# 04_MCU.net
KiCad netlist of a schematic drawn in Altium Designer
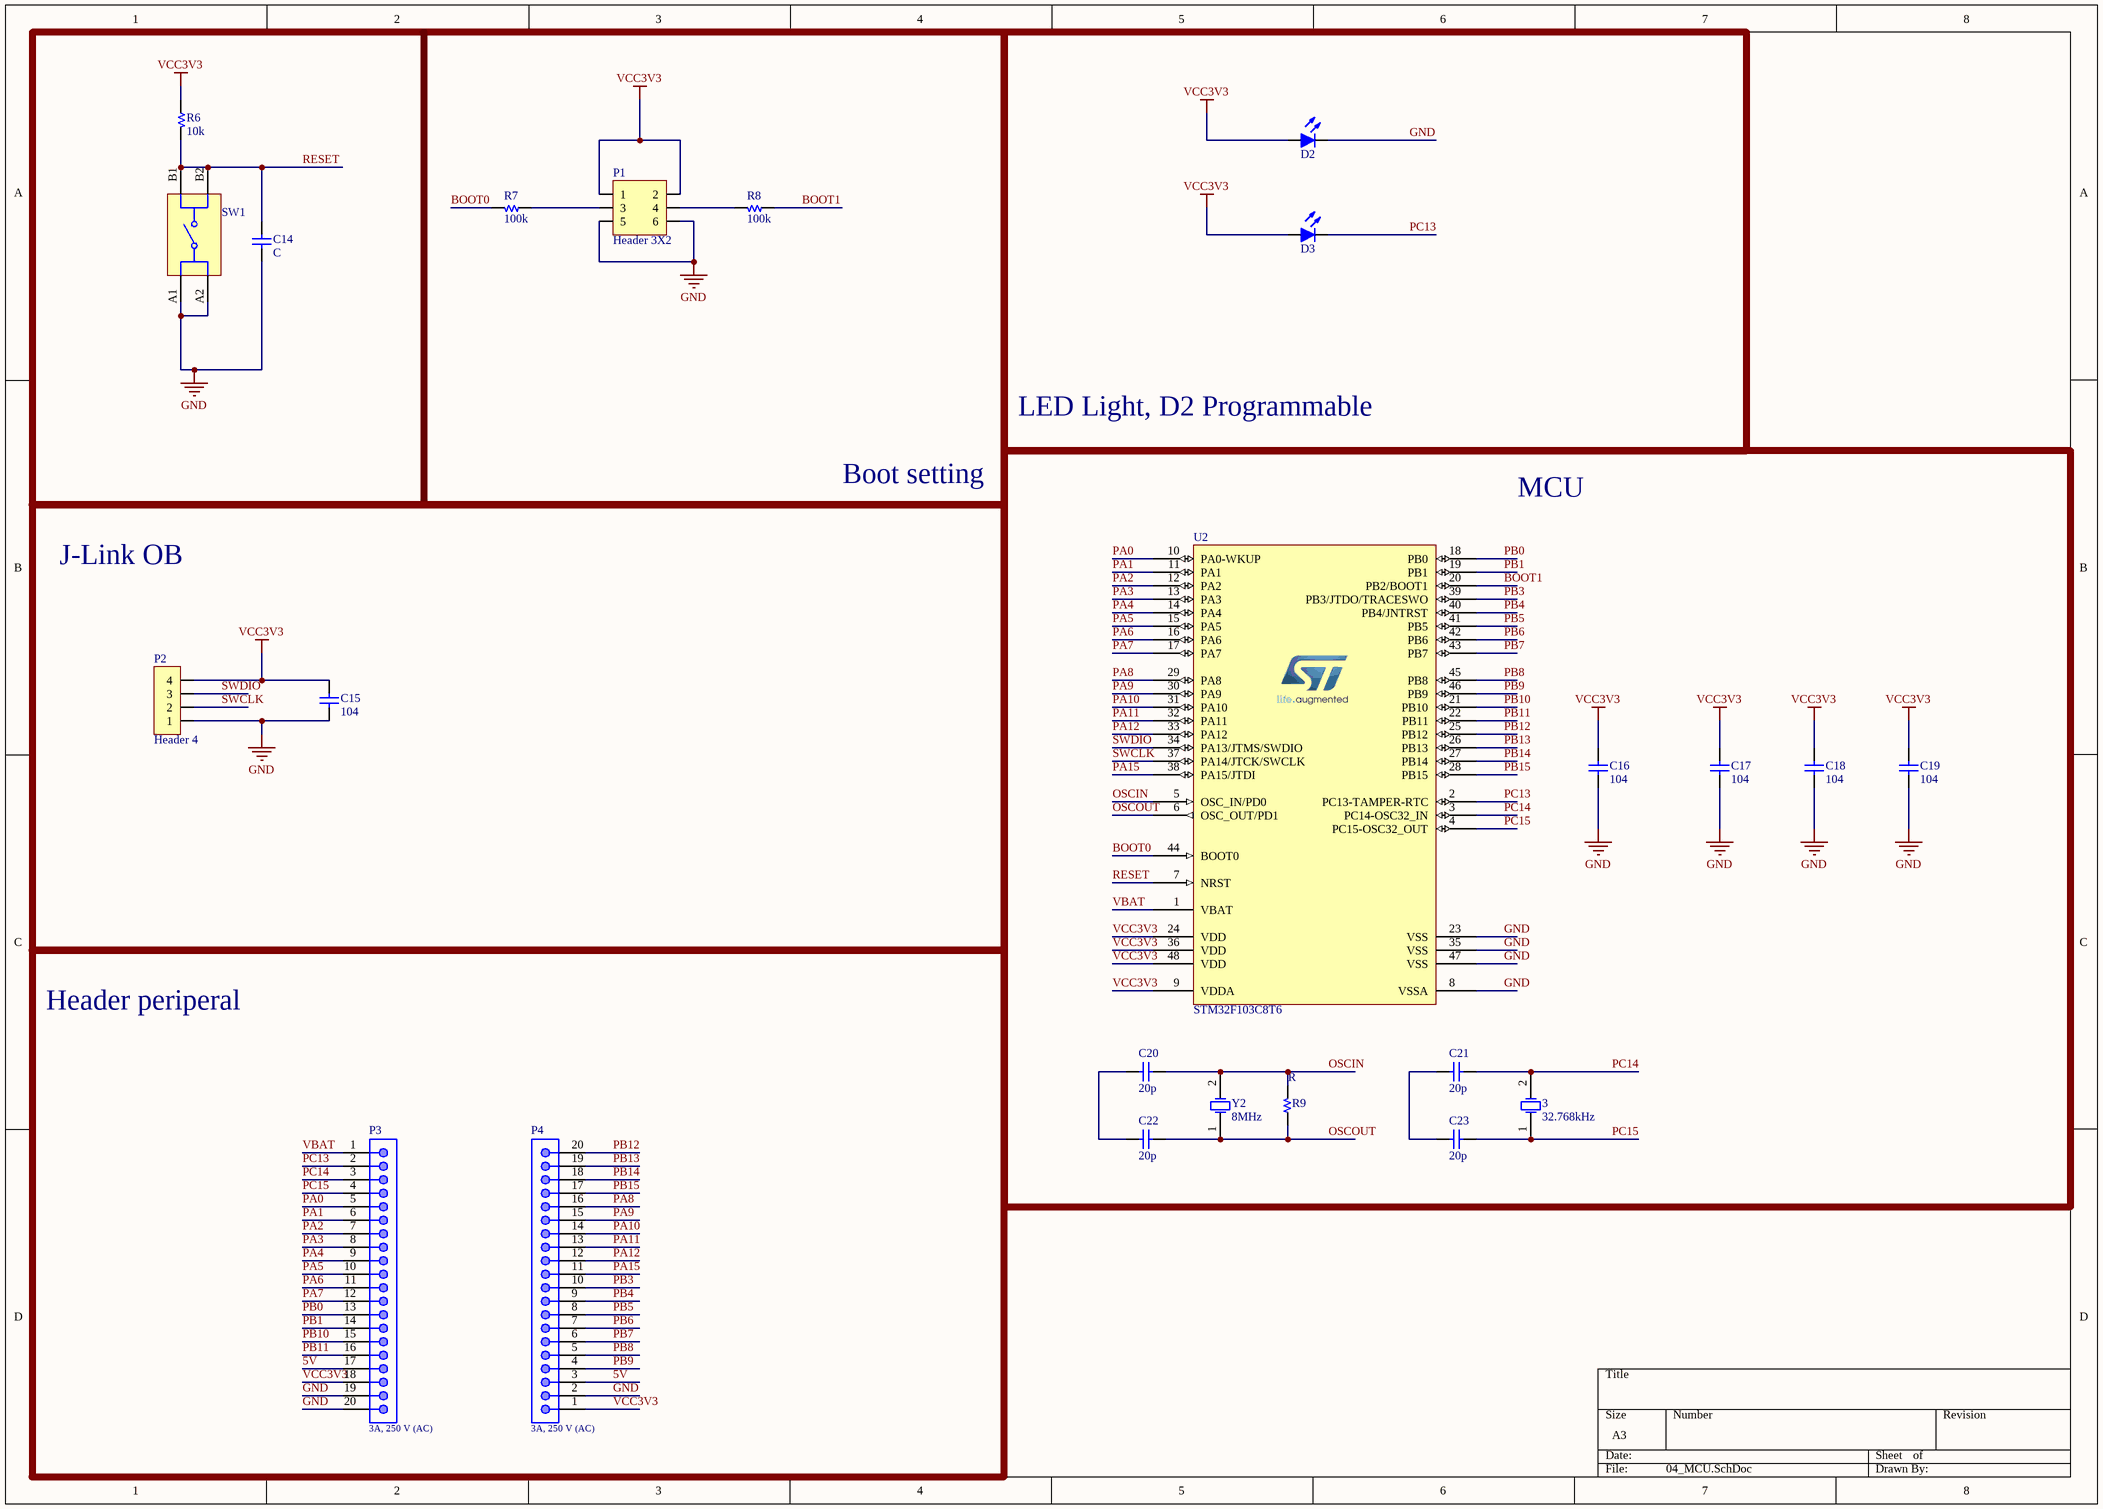
[diagram p0: 04_MCU.SchDoc]

(export (version "E")
  (design (tool "Eeschema 10.0.6"))
  (components
    (comp (ref "3")
      (value "32.768kHz")
      (footprint "XKXGI-SUA-32.768K")
      (description "32.768kHz Surface Mount Crystal 12.5pF ±20ppm ±30ppm SMD3215-2P Crystals ROHS")
      (fields (field (name "LCSC PART #") "C5213671") (field (name "MANUFACTURER") "YXC Crystal Oscillators"))
      (libsource (lib "Altium_XTAL_WATCH") (part "XKXGI-SUA-32.768K"))
    )
    (comp (ref "C14")
      (value "C")
      (footprint "C 0805")
      (description "Capacitor non-pol")
      (libsource (lib "chipfc_libs") (part "Capacitor NP"))
    )
    (comp (ref "C15")
      (value "104")
      (footprint "C 0805")
      (description "Capacitor non-pol")
      (libsource (lib "chipfc_libs") (part "Capacitor NP"))
    )
    (comp (ref "C16")
      (value "104")
      (footprint "C 0805")
      (description "Capacitor non-pol")
      (libsource (lib "chipfc_libs") (part "Capacitor NP"))
    )
    (comp (ref "C17")
      (value "104")
      (footprint "C 0805")
      (description "Capacitor non-pol")
      (libsource (lib "chipfc_libs") (part "Capacitor NP"))
    )
    (comp (ref "C18")
      (value "104")
      (footprint "C 0805")
      (description "Capacitor non-pol")
      (libsource (lib "chipfc_libs") (part "Capacitor NP"))
    )
    (comp (ref "C19")
      (value "104")
      (footprint "C 0805")
      (description "Capacitor non-pol")
      (libsource (lib "chipfc_libs") (part "Capacitor NP"))
    )
    (comp (ref "C20")
      (value "20p")
      (footprint "C 0805")
      (description "Capacitor non-pol")
      (libsource (lib "chipfc_libs") (part "Capacitor NP"))
    )
    (comp (ref "C21")
      (value "20p")
      (footprint "C 0805")
      (description "Capacitor non-pol")
      (libsource (lib "chipfc_libs") (part "Capacitor NP"))
    )
    (comp (ref "C22")
      (value "20p")
      (footprint "C 0805")
      (description "Capacitor non-pol")
      (libsource (lib "chipfc_libs") (part "Capacitor NP"))
    )
    (comp (ref "C23")
      (value "20p")
      (footprint "C 0805")
      (description "Capacitor non-pol")
      (libsource (lib "chipfc_libs") (part "Capacitor NP"))
    )
    (comp (ref "D2")
      (value "Led")
      (footprint "Led 0805")
      (description "Typical LED")
      (libsource (lib "led") (part "Led"))
    )
    (comp (ref "D3")
      (value "Led")
      (footprint "Led 0805")
      (description "Typical LED")
      (libsource (lib "led") (part "Led"))
    )
    (comp (ref "P1")
      (value "Header 3X2")
      (footprint "HDR/Header/6/DL")
      (description "Header, 3-Pin, Dual row")
      (libsource (lib "connectors") (part "Header 3X2"))
    )
    (comp (ref "P2")
      (value "Header 4")
      (footprint "HDR/Header/4")
      (description "Header, 4-Pin")
      (libsource (lib "connectors") (part "Header 4"))
    )
    (comp (ref "P3")
      (value "3A, 250 V (AC)")
      (footprint "61302011121")
      (description "WR-PHD Pin Header, THT, pitch 2.54mm, Single Row, Vertical, 20p")
      (fields
        (field (name "MANUFACTURER PART NUMBER") "61302011121")
        (field (name "MANUFACTURER") "Wurth Elektronik")
      )
      (libsource (lib "WR-PHD_Pin Header_2.54mm") (part "61302011121"))
    )
    (comp (ref "P4")
      (value "3A, 250 V (AC)")
      (footprint "61302011121")
      (description "WR-PHD Pin Header, THT, pitch 2.54mm, Single Row, Vertical, 20p")
      (fields
        (field (name "MANUFACTURER PART NUMBER") "61302011121")
        (field (name "MANUFACTURER") "Wurth Elektronik")
      )
      (libsource (lib "WR-PHD_Pin Header_2.54mm") (part "61302011121"))
    )
    (comp (ref "R6")
      (value "10k")
      (footprint "R 0805")
      (description "Resistor")
      (libsource (lib "chipfc_libs") (part "Resistor"))
    )
    (comp (ref "R7")
      (value "100k")
      (footprint "R 0805")
      (description "Resistor")
      (libsource (lib "chipfc_libs") (part "Resistor"))
    )
    (comp (ref "R8")
      (value "100k")
      (footprint "R 0805")
      (description "Resistor")
      (libsource (lib "chipfc_libs") (part "Resistor"))
    )
    (comp (ref "R9")
      (value "R")
      (footprint "R 0805")
      (description "Resistor")
      (libsource (lib "chipfc_libs") (part "Resistor"))
    )
    (comp (ref "SW1")
      (value "430152043826")
      (footprint "WS-TASV_L6W6H4.3_4301x20438x6")
      (description "WS-TASV SMT Tact Switch, L6 x W6 x H4.3mm, 260g, SPST-NO, 12V, 50mA")
      (fields (field (name "MANUFACTURER") "Wurth Elektronik"))
      (libsource (lib "Button") (part "430152043826"))
    )
    (comp (ref "U2")
      (value "STM32F103C8T6")
      (footprint "STM32F103C8T6")
      (description "ARM Microcontrollers - MCU 32BIT Cortex M3 64KB 20KB RAM 2X12 ADC")
      (fields
        (field (name "MANUFACTURER") "STMicroelectronics")
        (field (name "MANUFACTURER PART NUMBER") "STM32F103C8T6TR")
      )
      (libsource (lib "STM32") (part "STM32F103C8T6"))
    )
    (comp (ref "Y2")
      (value "8MHz")
      (footprint "WE-XTAL_HC49/4HSMX")
      (description "WE-XTAL Quartz Crystal, SMT, HC49/4HSMX, 8MHz, +/-30ppm")
      (fields
        (field (name "MANUFACTURER PART NUMBER") "830003151")
        (field (name "MANUFACTURER") "Wurth Elektronik")
      )
      (libsource (lib "Altium_XTAL_2PIN") (part "071105086016"))
    )
  )
  (nets
    (net (code "1") (name "/5V") (class "Default")
      (node (ref "P3") (pin "17") (pinfunction "17_17") (pintype "passive"))
      (node (ref "P4") (pin "3") (pinfunction "3_3") (pintype "passive"))
    )
    (net (code "2") (name "/BOOT0") (class "Default")
      (node (ref "R7") (pin "2") (pinfunction "2_2") (pintype "passive"))
      (node (ref "U2") (pin "44") (pinfunction "BOOT0_44") (pintype "input"))
    )
    (net (code "3") (name "/BOOT1") (class "Default")
      (node (ref "R8") (pin "1") (pinfunction "1_1") (pintype "passive"))
      (node (ref "U2") (pin "20") (pinfunction "PB2/BOOT1_20") (pintype "bidirectional"))
    )
    (net (code "4") (name "/OSCIN") (class "Default")
      (node (ref "C20") (pin "1") (pinfunction "1_1") (pintype "passive"))
      (node (ref "R9") (pin "2") (pinfunction "2_2") (pintype "passive"))
      (node (ref "U2") (pin "5") (pinfunction "OSC_IN/PD0_5") (pintype "input"))
      (node (ref "Y2") (pin "2") (pinfunction "OSC2_2") (pintype "passive"))
    )
    (net (code "5") (name "/OSCOUT") (class "Default")
      (node (ref "C22") (pin "1") (pinfunction "1_1") (pintype "passive"))
      (node (ref "R9") (pin "1") (pinfunction "1_1") (pintype "passive"))
      (node (ref "U2") (pin "6") (pinfunction "OSC_OUT/PD1_6") (pintype "output"))
      (node (ref "Y2") (pin "1") (pinfunction "OSC1_1") (pintype "passive"))
    )
    (net (code "6") (name "/PA0") (class "Default")
      (node (ref "P3") (pin "5") (pinfunction "5_5") (pintype "passive"))
      (node (ref "U2") (pin "10") (pinfunction "PA0-WKUP_10") (pintype "bidirectional"))
    )
    (net (code "7") (name "/PA1") (class "Default")
      (node (ref "P3") (pin "6") (pinfunction "6_6") (pintype "passive"))
      (node (ref "U2") (pin "11") (pinfunction "PA1_11") (pintype "bidirectional"))
    )
    (net (code "8") (name "/PA2") (class "Default")
      (node (ref "P3") (pin "7") (pinfunction "7_7") (pintype "passive"))
      (node (ref "U2") (pin "12") (pinfunction "PA2_12") (pintype "bidirectional"))
    )
    (net (code "9") (name "/PA3") (class "Default")
      (node (ref "P3") (pin "8") (pinfunction "8_8") (pintype "passive"))
      (node (ref "U2") (pin "13") (pinfunction "PA3_13") (pintype "bidirectional"))
    )
    (net (code "10") (name "/PA4") (class "Default")
      (node (ref "P3") (pin "9") (pinfunction "9_9") (pintype "passive"))
      (node (ref "U2") (pin "14") (pinfunction "PA4_14") (pintype "bidirectional"))
    )
    (net (code "11") (name "/PA5") (class "Default")
      (node (ref "P3") (pin "10") (pinfunction "10_10") (pintype "passive"))
      (node (ref "U2") (pin "15") (pinfunction "PA5_15") (pintype "bidirectional"))
    )
    (net (code "12") (name "/PA6") (class "Default")
      (node (ref "P3") (pin "11") (pinfunction "11_11") (pintype "passive"))
      (node (ref "U2") (pin "16") (pinfunction "PA6_16") (pintype "bidirectional"))
    )
    (net (code "13") (name "/PA7") (class "Default")
      (node (ref "P3") (pin "12") (pinfunction "12_12") (pintype "passive"))
      (node (ref "U2") (pin "17") (pinfunction "PA7_17") (pintype "bidirectional"))
    )
    (net (code "14") (name "/PA8") (class "Default")
      (node (ref "P4") (pin "16") (pinfunction "16_16") (pintype "passive"))
      (node (ref "U2") (pin "29") (pinfunction "PA8_29") (pintype "bidirectional"))
    )
    (net (code "15") (name "/PA9") (class "Default")
      (node (ref "P4") (pin "15") (pinfunction "15_15") (pintype "passive"))
      (node (ref "U2") (pin "30") (pinfunction "PA9_30") (pintype "bidirectional"))
    )
    (net (code "16") (name "/PA10") (class "Default")
      (node (ref "P4") (pin "14") (pinfunction "14_14") (pintype "passive"))
      (node (ref "U2") (pin "31") (pinfunction "PA10_31") (pintype "bidirectional"))
    )
    (net (code "17") (name "/PA11") (class "Default")
      (node (ref "P4") (pin "13") (pinfunction "13_13") (pintype "passive"))
      (node (ref "U2") (pin "32") (pinfunction "PA11_32") (pintype "bidirectional"))
    )
    (net (code "18") (name "/PA12") (class "Default")
      (node (ref "P4") (pin "12") (pinfunction "12_12") (pintype "passive"))
      (node (ref "U2") (pin "33") (pinfunction "PA12_33") (pintype "bidirectional"))
    )
    (net (code "19") (name "/PA15") (class "Default")
      (node (ref "P4") (pin "11") (pinfunction "11_11") (pintype "passive"))
      (node (ref "U2") (pin "38") (pinfunction "PA15/JTDI_38") (pintype "bidirectional"))
    )
    (net (code "20") (name "/PB0") (class "Default")
      (node (ref "P3") (pin "13") (pinfunction "13_13") (pintype "passive"))
      (node (ref "U2") (pin "18") (pinfunction "PB0_18") (pintype "bidirectional"))
    )
    (net (code "21") (name "/PB1") (class "Default")
      (node (ref "P3") (pin "14") (pinfunction "14_14") (pintype "passive"))
      (node (ref "U2") (pin "19") (pinfunction "PB1_19") (pintype "bidirectional"))
    )
    (net (code "22") (name "/PB3") (class "Default")
      (node (ref "P4") (pin "10") (pinfunction "10_10") (pintype "passive"))
      (node (ref "U2") (pin "39") (pinfunction "PB3/JTDO/TRACESWO_39") (pintype "bidirectional"))
    )
    (net (code "23") (name "/PB4") (class "Default")
      (node (ref "P4") (pin "9") (pinfunction "9_9") (pintype "passive"))
      (node (ref "U2") (pin "40") (pinfunction "PB4/JNTRST_40") (pintype "bidirectional"))
    )
    (net (code "24") (name "/PB5") (class "Default")
      (node (ref "P4") (pin "8") (pinfunction "8_8") (pintype "passive"))
      (node (ref "U2") (pin "41") (pinfunction "PB5_41") (pintype "bidirectional"))
    )
    (net (code "25") (name "/PB6") (class "Default")
      (node (ref "P4") (pin "7") (pinfunction "7_7") (pintype "passive"))
      (node (ref "U2") (pin "42") (pinfunction "PB6_42") (pintype "bidirectional"))
    )
    (net (code "26") (name "/PB7") (class "Default")
      (node (ref "P4") (pin "6") (pinfunction "6_6") (pintype "passive"))
      (node (ref "U2") (pin "43") (pinfunction "PB7_43") (pintype "bidirectional"))
    )
    (net (code "27") (name "/PB8") (class "Default")
      (node (ref "P4") (pin "5") (pinfunction "5_5") (pintype "passive"))
      (node (ref "U2") (pin "45") (pinfunction "PB8_45") (pintype "bidirectional"))
    )
    (net (code "28") (name "/PB9") (class "Default")
      (node (ref "P4") (pin "4") (pinfunction "4_4") (pintype "passive"))
      (node (ref "U2") (pin "46") (pinfunction "PB9_46") (pintype "bidirectional"))
    )
    (net (code "29") (name "/PB10") (class "Default")
      (node (ref "P3") (pin "15") (pinfunction "15_15") (pintype "passive"))
      (node (ref "U2") (pin "21") (pinfunction "PB10_21") (pintype "bidirectional"))
    )
    (net (code "30") (name "/PB11") (class "Default")
      (node (ref "P3") (pin "16") (pinfunction "16_16") (pintype "passive"))
      (node (ref "U2") (pin "22") (pinfunction "PB11_22") (pintype "bidirectional"))
    )
    (net (code "31") (name "/PB12") (class "Default")
      (node (ref "P4") (pin "20") (pinfunction "20_20") (pintype "passive"))
      (node (ref "U2") (pin "25") (pinfunction "PB12_25") (pintype "bidirectional"))
    )
    (net (code "32") (name "/PB13") (class "Default")
      (node (ref "P4") (pin "19") (pinfunction "19_19") (pintype "passive"))
      (node (ref "U2") (pin "26") (pinfunction "PB13_26") (pintype "bidirectional"))
    )
    (net (code "33") (name "/PB14") (class "Default")
      (node (ref "P4") (pin "18") (pinfunction "18_18") (pintype "passive"))
      (node (ref "U2") (pin "27") (pinfunction "PB14_27") (pintype "bidirectional"))
    )
    (net (code "34") (name "/PB15") (class "Default")
      (node (ref "P4") (pin "17") (pinfunction "17_17") (pintype "passive"))
      (node (ref "U2") (pin "28") (pinfunction "PB15_28") (pintype "bidirectional"))
    )
    (net (code "35") (name "/PC13") (class "Default")
      (node (ref "D3") (pin "2") (pinfunction "K_2") (pintype "passive"))
      (node (ref "P3") (pin "2") (pinfunction "2_2") (pintype "passive"))
      (node (ref "U2") (pin "2") (pinfunction "PC13-TAMPER-RTC_2") (pintype "bidirectional"))
    )
    (net (code "36") (name "/PC14") (class "Default")
      (node (ref "3") (pin "2") (pinfunction "OSC2_2") (pintype "passive"))
      (node (ref "C21") (pin "1") (pinfunction "1_1") (pintype "passive"))
      (node (ref "P3") (pin "3") (pinfunction "3_3") (pintype "passive"))
      (node (ref "U2") (pin "3") (pinfunction "PC14-OSC32_IN_3") (pintype "bidirectional"))
    )
    (net (code "37") (name "/PC15") (class "Default")
      (node (ref "3") (pin "1") (pinfunction "OSC1_1") (pintype "passive"))
      (node (ref "C23") (pin "1") (pinfunction "1_1") (pintype "passive"))
      (node (ref "P3") (pin "4") (pinfunction "4_4") (pintype "passive"))
      (node (ref "U2") (pin "4") (pinfunction "PC15-OSC32_OUT_4") (pintype "bidirectional"))
    )
    (net (code "38") (name "/RESET") (class "Default")
      (node (ref "C14") (pin "1") (pinfunction "1_1") (pintype "passive"))
      (node (ref "R6") (pin "2") (pinfunction "2_2") (pintype "passive"))
      (node (ref "SW1") (pin "B1") (pinfunction "B1_B1") (pintype "passive"))
      (node (ref "SW1") (pin "B2") (pinfunction "B2_B2") (pintype "passive"))
      (node (ref "U2") (pin "7") (pinfunction "NRST_7") (pintype "input"))
    )
    (net (code "39") (name "/SWCLK") (class "Default")
      (node (ref "P2") (pin "2") (pinfunction "2_2") (pintype "passive"))
      (node (ref "U2") (pin "37") (pinfunction "PA14/JTCK/SWCLK_37") (pintype "bidirectional"))
    )
    (net (code "40") (name "/SWDIO") (class "Default")
      (node (ref "P2") (pin "3") (pinfunction "3_3") (pintype "passive"))
      (node (ref "U2") (pin "34") (pinfunction "PA13/JTMS/SWDIO_34") (pintype "bidirectional"))
    )
    (net (code "41") (name "/VBAT") (class "Default")
      (node (ref "P3") (pin "1") (pinfunction "1_1") (pintype "passive"))
      (node (ref "U2") (pin "1") (pinfunction "VBAT_1") (pintype "power_in"))
    )
    (net (code "42") (name "GND") (class "Default")
      (node (ref "C14") (pin "2") (pinfunction "2_2") (pintype "passive"))
      (node (ref "C15") (pin "2") (pinfunction "2_2") (pintype "passive"))
      (node (ref "C16") (pin "1") (pinfunction "1_1") (pintype "passive"))
      (node (ref "C17") (pin "1") (pinfunction "1_1") (pintype "passive"))
      (node (ref "C18") (pin "1") (pinfunction "1_1") (pintype "passive"))
      (node (ref "C19") (pin "1") (pinfunction "1_1") (pintype "passive"))
      (node (ref "D2") (pin "2") (pinfunction "K_2") (pintype "passive"))
      (node (ref "P1") (pin "5") (pinfunction "5_5") (pintype "passive"))
      (node (ref "P1") (pin "6") (pinfunction "6_6") (pintype "passive"))
      (node (ref "P2") (pin "1") (pinfunction "1_1") (pintype "passive"))
      (node (ref "P3") (pin "19") (pinfunction "19_19") (pintype "passive"))
      (node (ref "P3") (pin "20") (pinfunction "20_20") (pintype "passive"))
      (node (ref "P4") (pin "2") (pinfunction "2_2") (pintype "passive"))
      (node (ref "SW1") (pin "A1") (pinfunction "A1_A1") (pintype "passive"))
      (node (ref "SW1") (pin "A2") (pinfunction "A2_A2") (pintype "passive"))
      (node (ref "U2") (pin "23") (pinfunction "VSS_23") (pintype "power_in"))
      (node (ref "U2") (pin "35") (pinfunction "VSS_35") (pintype "power_in"))
      (node (ref "U2") (pin "47") (pinfunction "VSS_47") (pintype "power_in"))
      (node (ref "U2") (pin "8") (pinfunction "VSSA_8") (pintype "power_in"))
    )
    (net (code "43") (name "Net-(C20-Pad2)") (class "Default")
      (node (ref "C20") (pin "2") (pinfunction "2_2") (pintype "passive"))
      (node (ref "C22") (pin "2") (pinfunction "2_2") (pintype "passive"))
    )
    (net (code "44") (name "Net-(C21-Pad2)") (class "Default")
      (node (ref "C21") (pin "2") (pinfunction "2_2") (pintype "passive"))
      (node (ref "C23") (pin "2") (pinfunction "2_2") (pintype "passive"))
    )
    (net (code "45") (name "Net-(P1-Pad3)") (class "Default")
      (node (ref "P1") (pin "3") (pinfunction "3_3") (pintype "passive"))
      (node (ref "R7") (pin "1") (pinfunction "1_1") (pintype "passive"))
    )
    (net (code "46") (name "Net-(P1-Pad4)") (class "Default")
      (node (ref "P1") (pin "4") (pinfunction "4_4") (pintype "passive"))
      (node (ref "R8") (pin "2") (pinfunction "2_2") (pintype "passive"))
    )
    (net (code "47") (name "VCC3V3") (class "Default")
      (node (ref "C15") (pin "1") (pinfunction "1_1") (pintype "passive"))
      (node (ref "C16") (pin "2") (pinfunction "2_2") (pintype "passive"))
      (node (ref "C17") (pin "2") (pinfunction "2_2") (pintype "passive"))
      (node (ref "C18") (pin "2") (pinfunction "2_2") (pintype "passive"))
      (node (ref "C19") (pin "2") (pinfunction "2_2") (pintype "passive"))
      (node (ref "D2") (pin "1") (pinfunction "A_1") (pintype "passive"))
      (node (ref "D3") (pin "1") (pinfunction "A_1") (pintype "passive"))
      (node (ref "P1") (pin "1") (pinfunction "1_1") (pintype "passive"))
      (node (ref "P1") (pin "2") (pinfunction "2_2") (pintype "passive"))
      (node (ref "P2") (pin "4") (pinfunction "4_4") (pintype "passive"))
      (node (ref "P3") (pin "18") (pinfunction "18_18") (pintype "passive"))
      (node (ref "P4") (pin "1") (pinfunction "1_1") (pintype "passive"))
      (node (ref "R6") (pin "1") (pinfunction "1_1") (pintype "passive"))
      (node (ref "U2") (pin "24") (pinfunction "VDD_24") (pintype "power_in"))
      (node (ref "U2") (pin "36") (pinfunction "VDD_36") (pintype "power_in"))
      (node (ref "U2") (pin "48") (pinfunction "VDD_48") (pintype "power_in"))
      (node (ref "U2") (pin "9") (pinfunction "VDDA_9") (pintype "power_in"))
    )
  )
)
